# JTAG.net
KiCad netlist of a schematic drawn in Altium Designer
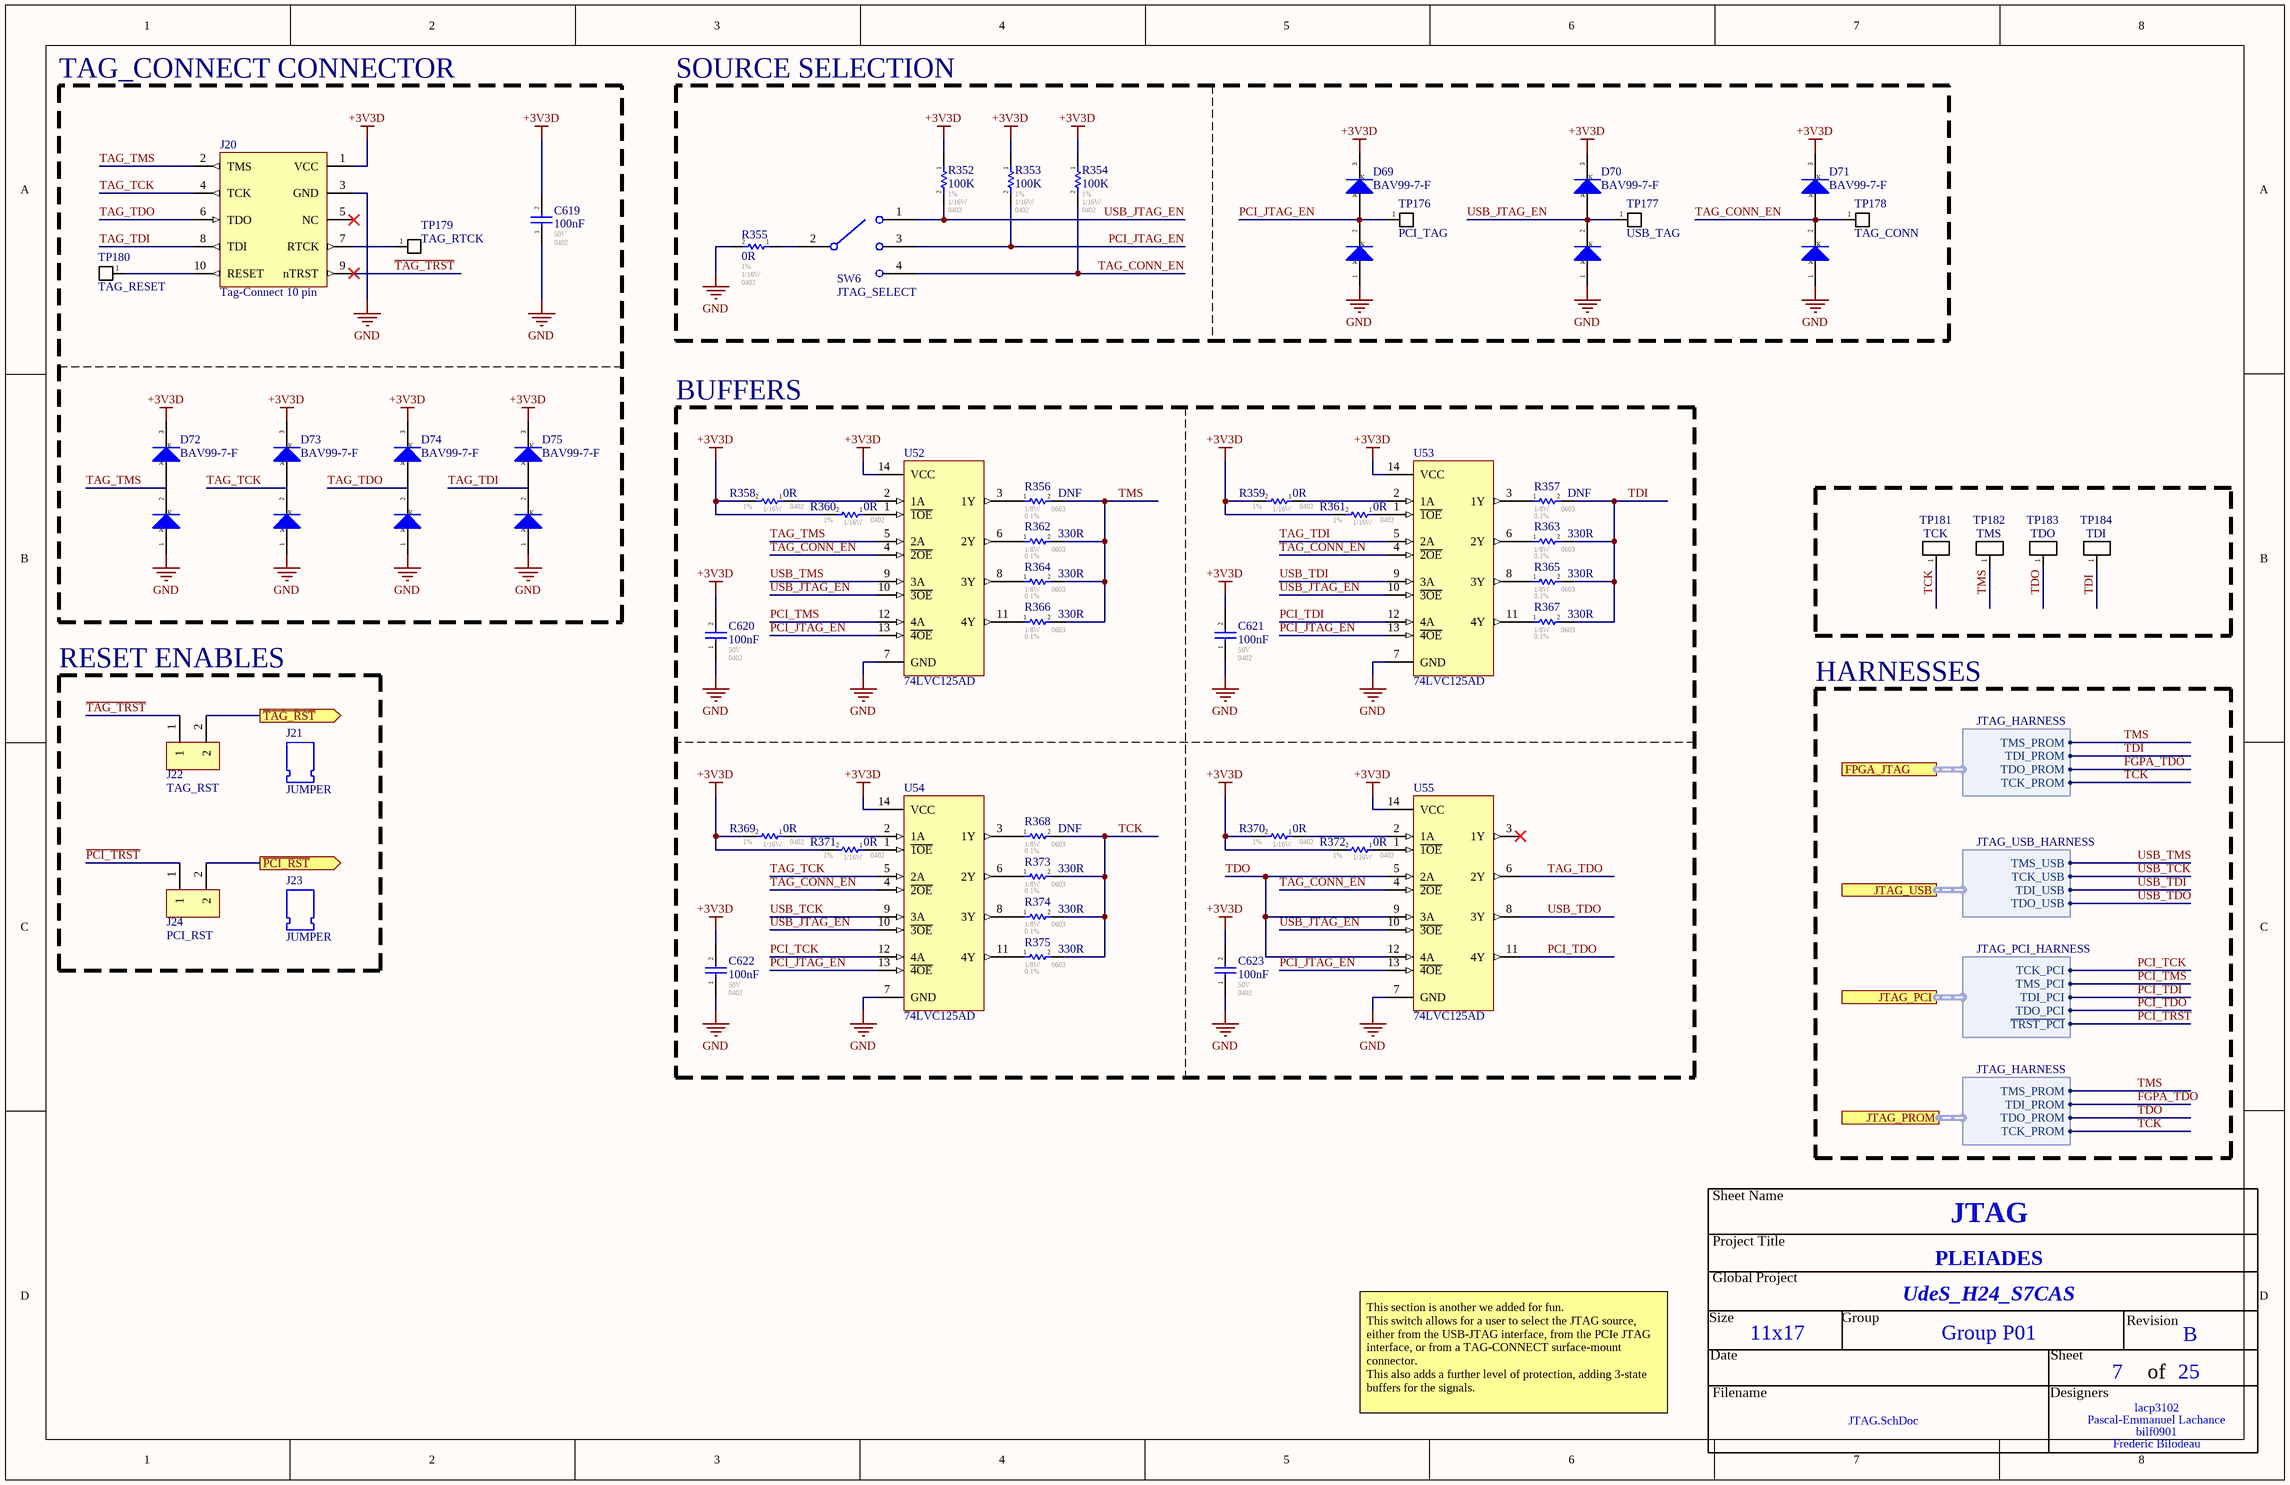
[diagram p0: JTAG.SchDoc]

(export (version "E")
  (design (tool "Eeschema 10.0.6"))
  (components
    (comp (ref "C619")
      (value "100nF")
      (footprint "0402")
      (description "GCM155R71H104KE02J\r\n0402 100nF 10% X7R Ceramic Capacitor")
      (fields
        (field (name "MFR") "Murata")
        (field (name "PART#") "GCM155R71H104KE02J")
        (field (name "VOLTAGE - RATED") "50V")
      )
      (libsource (lib "Symbols") (part "CAP_CER"))
    )
    (comp (ref "C620")
      (value "100nF")
      (footprint "0402")
      (description "GCM155R71H104KE02J\r\n0402 100nF 10% X7R Ceramic Capacitor")
      (fields
        (field (name "MFR") "Murata")
        (field (name "PART#") "GCM155R71H104KE02J")
        (field (name "VOLTAGE - RATED") "50V")
      )
      (libsource (lib "Symbols") (part "CAP_CER"))
    )
    (comp (ref "C621")
      (value "100nF")
      (footprint "0402")
      (description "GCM155R71H104KE02J\r\n0402 100nF 10% X7R Ceramic Capacitor")
      (fields
        (field (name "MFR") "Murata")
        (field (name "PART#") "GCM155R71H104KE02J")
        (field (name "VOLTAGE - RATED") "50V")
      )
      (libsource (lib "Symbols") (part "CAP_CER"))
    )
    (comp (ref "C622")
      (value "100nF")
      (footprint "0402")
      (description "GCM155R71H104KE02J\r\n0402 100nF 10% X7R Ceramic Capacitor")
      (fields
        (field (name "MFR") "Murata")
        (field (name "PART#") "GCM155R71H104KE02J")
        (field (name "VOLTAGE - RATED") "50V")
      )
      (libsource (lib "Symbols") (part "CAP_CER"))
    )
    (comp (ref "C623")
      (value "100nF")
      (footprint "0402")
      (description "GCM155R71H104KE02J\r\n0402 100nF 10% X7R Ceramic Capacitor")
      (fields
        (field (name "MFR") "Murata")
        (field (name "PART#") "GCM155R71H104KE02J")
        (field (name "VOLTAGE - RATED") "50V")
      )
      (libsource (lib "Symbols") (part "CAP_CER"))
    )
    (comp (ref "D69")
      (value "BAV99-7-F")
      (footprint "SOT23-3")
      (description "Diode Array 1 Pair Series Connection 75 V 300mA (DC) Surface Mount TO-236-3, SC-59, SOT-23-3")
      (fields (field (name "MFR") "Diodes Incorporated"))
      (libsource (lib "Symbols") (part "DIODE_TVS_DUAL"))
    )
    (comp (ref "D70")
      (value "BAV99-7-F")
      (footprint "SOT23-3")
      (description "Diode Array 1 Pair Series Connection 75 V 300mA (DC) Surface Mount TO-236-3, SC-59, SOT-23-3")
      (fields (field (name "MFR") "Diodes Incorporated"))
      (libsource (lib "Symbols") (part "DIODE_TVS_DUAL"))
    )
    (comp (ref "D71")
      (value "BAV99-7-F")
      (footprint "SOT23-3")
      (description "Diode Array 1 Pair Series Connection 75 V 300mA (DC) Surface Mount TO-236-3, SC-59, SOT-23-3")
      (fields (field (name "MFR") "Diodes Incorporated"))
      (libsource (lib "Symbols") (part "DIODE_TVS_DUAL"))
    )
    (comp (ref "D72")
      (value "BAV99-7-F")
      (footprint "SOT23-3")
      (description "Diode Array 1 Pair Series Connection 75 V 300mA (DC) Surface Mount TO-236-3, SC-59, SOT-23-3")
      (fields (field (name "MFR") "Diodes Incorporated"))
      (libsource (lib "Symbols") (part "DIODE_TVS_DUAL"))
    )
    (comp (ref "D73")
      (value "BAV99-7-F")
      (footprint "SOT23-3")
      (description "Diode Array 1 Pair Series Connection 75 V 300mA (DC) Surface Mount TO-236-3, SC-59, SOT-23-3")
      (fields (field (name "MFR") "Diodes Incorporated"))
      (libsource (lib "Symbols") (part "DIODE_TVS_DUAL"))
    )
    (comp (ref "D74")
      (value "BAV99-7-F")
      (footprint "SOT23-3")
      (description "Diode Array 1 Pair Series Connection 75 V 300mA (DC) Surface Mount TO-236-3, SC-59, SOT-23-3")
      (fields (field (name "MFR") "Diodes Incorporated"))
      (libsource (lib "Symbols") (part "DIODE_TVS_DUAL"))
    )
    (comp (ref "D75")
      (value "BAV99-7-F")
      (footprint "SOT23-3")
      (description "Diode Array 1 Pair Series Connection 75 V 300mA (DC) Surface Mount TO-236-3, SC-59, SOT-23-3")
      (fields (field (name "MFR") "Diodes Incorporated"))
      (libsource (lib "Symbols") (part "DIODE_TVS_DUAL"))
    )
    (comp (ref "J20")
      (value "Tag-Connect 10 pin")
      (footprint "TC2050-NL")
      (libsource (lib "Connectors") (part "TC2050-NL"))
    )
    (comp (ref "J21") (value "JUMPER") (libsource (lib "Misc") (part "JUMPER")))
    (comp (ref "J22")
      (value "TAG_RST")
      (footprint "HEADER-2_100MIL")
      (libsource (lib "Connectors") (part "HEADER_2"))
    )
    (comp (ref "J23") (value "JUMPER") (libsource (lib "Misc") (part "JUMPER")))
    (comp (ref "J24")
      (value "PCI_RST")
      (footprint "HEADER-2_100MIL")
      (libsource (lib "Connectors") (part "HEADER_2"))
    )
    (comp (ref "R352")
      (value "100K")
      (footprint "RES_0402")
      (fields
        (field (name "TOLERANCE") "1%")
        (field (name "POWER") "1/16W")
        (field (name "PACKAGE / CASE") "0402")
      )
      (libsource (lib "Symbols") (part "RESISTOR"))
    )
    (comp (ref "R353")
      (value "100K")
      (footprint "RES_0402")
      (fields
        (field (name "TOLERANCE") "1%")
        (field (name "POWER") "1/16W")
        (field (name "PACKAGE / CASE") "0402")
      )
      (libsource (lib "Symbols") (part "RESISTOR"))
    )
    (comp (ref "R354")
      (value "100K")
      (footprint "RES_0402")
      (fields
        (field (name "TOLERANCE") "1%")
        (field (name "POWER") "1/16W")
        (field (name "PACKAGE / CASE") "0402")
      )
      (libsource (lib "Symbols") (part "RESISTOR"))
    )
    (comp (ref "R355")
      (value "0R")
      (footprint "RES_0402")
      (fields
        (field (name "TOLERANCE") "1%")
        (field (name "POWER") "1/16W")
        (field (name "PACKAGE / CASE") "0402")
      )
      (libsource (lib "Symbols") (part "RESISTOR"))
    )
    (comp (ref "R356")
      (value "DNF")
      (footprint "RES_0603")
      (description "1M 0603 1% 1/16W Resistor")
      (fields
        (field (name "TOLERANCE") "0.1%")
        (field (name "POWER") "1/8W")
        (field (name "PACKAGE / CASE") "0603")
      )
      (libsource (lib "Symbols") (part "RESISTOR"))
    )
    (comp (ref "R357")
      (value "DNF")
      (footprint "RES_0603")
      (description "1M 0603 1% 1/16W Resistor")
      (fields
        (field (name "TOLERANCE") "0.1%")
        (field (name "POWER") "1/8W")
        (field (name "PACKAGE / CASE") "0603")
      )
      (libsource (lib "Symbols") (part "RESISTOR"))
    )
    (comp (ref "R358")
      (value "0R")
      (footprint "RES_0402")
      (fields
        (field (name "TOLERANCE") "1%")
        (field (name "POWER") "1/16W")
        (field (name "PACKAGE / CASE") "0402")
      )
      (libsource (lib "Symbols") (part "RESISTOR"))
    )
    (comp (ref "R359")
      (value "0R")
      (footprint "RES_0402")
      (fields
        (field (name "TOLERANCE") "1%")
        (field (name "POWER") "1/16W")
        (field (name "PACKAGE / CASE") "0402")
      )
      (libsource (lib "Symbols") (part "RESISTOR"))
    )
    (comp (ref "R360")
      (value "0R")
      (footprint "RES_0402")
      (fields
        (field (name "TOLERANCE") "1%")
        (field (name "POWER") "1/16W")
        (field (name "PACKAGE / CASE") "0402")
      )
      (libsource (lib "Symbols") (part "RESISTOR"))
    )
    (comp (ref "R361")
      (value "0R")
      (footprint "RES_0402")
      (fields
        (field (name "TOLERANCE") "1%")
        (field (name "POWER") "1/16W")
        (field (name "PACKAGE / CASE") "0402")
      )
      (libsource (lib "Symbols") (part "RESISTOR"))
    )
    (comp (ref "R362")
      (value "330R")
      (footprint "RES_0603")
      (description "1M 0603 1% 1/16W Resistor")
      (fields
        (field (name "TOLERANCE") "0.1%")
        (field (name "POWER") "1/8W")
        (field (name "PACKAGE / CASE") "0603")
      )
      (libsource (lib "Symbols") (part "RESISTOR"))
    )
    (comp (ref "R363")
      (value "330R")
      (footprint "RES_0603")
      (description "1M 0603 1% 1/16W Resistor")
      (fields
        (field (name "TOLERANCE") "0.1%")
        (field (name "POWER") "1/8W")
        (field (name "PACKAGE / CASE") "0603")
      )
      (libsource (lib "Symbols") (part "RESISTOR"))
    )
    (comp (ref "R364")
      (value "330R")
      (footprint "RES_0603")
      (description "1M 0603 1% 1/16W Resistor")
      (fields
        (field (name "TOLERANCE") "0.1%")
        (field (name "POWER") "1/8W")
        (field (name "PACKAGE / CASE") "0603")
      )
      (libsource (lib "Symbols") (part "RESISTOR"))
    )
    (comp (ref "R365")
      (value "330R")
      (footprint "RES_0603")
      (description "1M 0603 1% 1/16W Resistor")
      (fields
        (field (name "TOLERANCE") "0.1%")
        (field (name "POWER") "1/8W")
        (field (name "PACKAGE / CASE") "0603")
      )
      (libsource (lib "Symbols") (part "RESISTOR"))
    )
    (comp (ref "R366")
      (value "330R")
      (footprint "RES_0603")
      (description "1M 0603 1% 1/16W Resistor")
      (fields
        (field (name "TOLERANCE") "0.1%")
        (field (name "POWER") "1/8W")
        (field (name "PACKAGE / CASE") "0603")
      )
      (libsource (lib "Symbols") (part "RESISTOR"))
    )
    (comp (ref "R367")
      (value "330R")
      (footprint "RES_0603")
      (description "1M 0603 1% 1/16W Resistor")
      (fields
        (field (name "TOLERANCE") "0.1%")
        (field (name "POWER") "1/8W")
        (field (name "PACKAGE / CASE") "0603")
      )
      (libsource (lib "Symbols") (part "RESISTOR"))
    )
    (comp (ref "R368")
      (value "DNF")
      (footprint "RES_0603")
      (description "1M 0603 1% 1/16W Resistor")
      (fields
        (field (name "TOLERANCE") "0.1%")
        (field (name "POWER") "1/8W")
        (field (name "PACKAGE / CASE") "0603")
      )
      (libsource (lib "Symbols") (part "RESISTOR"))
    )
    (comp (ref "R369")
      (value "0R")
      (footprint "RES_0402")
      (fields
        (field (name "TOLERANCE") "1%")
        (field (name "POWER") "1/16W")
        (field (name "PACKAGE / CASE") "0402")
      )
      (libsource (lib "Symbols") (part "RESISTOR"))
    )
    (comp (ref "R370")
      (value "0R")
      (footprint "RES_0402")
      (fields
        (field (name "TOLERANCE") "1%")
        (field (name "POWER") "1/16W")
        (field (name "PACKAGE / CASE") "0402")
      )
      (libsource (lib "Symbols") (part "RESISTOR"))
    )
    (comp (ref "R371")
      (value "0R")
      (footprint "RES_0402")
      (fields
        (field (name "TOLERANCE") "1%")
        (field (name "POWER") "1/16W")
        (field (name "PACKAGE / CASE") "0402")
      )
      (libsource (lib "Symbols") (part "RESISTOR"))
    )
    (comp (ref "R372")
      (value "0R")
      (footprint "RES_0402")
      (fields
        (field (name "TOLERANCE") "1%")
        (field (name "POWER") "1/16W")
        (field (name "PACKAGE / CASE") "0402")
      )
      (libsource (lib "Symbols") (part "RESISTOR"))
    )
    (comp (ref "R373")
      (value "330R")
      (footprint "RES_0603")
      (description "1M 0603 1% 1/16W Resistor")
      (fields
        (field (name "TOLERANCE") "0.1%")
        (field (name "POWER") "1/8W")
        (field (name "PACKAGE / CASE") "0603")
      )
      (libsource (lib "Symbols") (part "RESISTOR"))
    )
    (comp (ref "R374")
      (value "330R")
      (footprint "RES_0603")
      (description "1M 0603 1% 1/16W Resistor")
      (fields
        (field (name "TOLERANCE") "0.1%")
        (field (name "POWER") "1/8W")
        (field (name "PACKAGE / CASE") "0603")
      )
      (libsource (lib "Symbols") (part "RESISTOR"))
    )
    (comp (ref "R375")
      (value "330R")
      (footprint "RES_0603")
      (description "1M 0603 1% 1/16W Resistor")
      (fields
        (field (name "TOLERANCE") "0.1%")
        (field (name "POWER") "1/8W")
        (field (name "PACKAGE / CASE") "0603")
      )
      (libsource (lib "Symbols") (part "RESISTOR"))
    )
    (comp (ref "SW6")
      (value "JTAG_SELECT")
      (footprint "1825256-6")
      (description "1825256-6\r\nSlide Switch SP3T Through Hole, Right Angle")
      (fields (field (name "MFR") "TE Connectivity"))
      (libsource (lib "Symbols") (part "SP3T_SWITCH"))
    )
    (comp (ref "TP176")
      (value "PCI_TAG")
      (footprint "TP_PAD")
      (description "Test Point")
      (libsource (lib "Symbols") (part "TESTPOINT_PAD"))
    )
    (comp (ref "TP177")
      (value "USB_TAG")
      (footprint "TP_PAD")
      (description "Test Point")
      (libsource (lib "Symbols") (part "TESTPOINT_PAD"))
    )
    (comp (ref "TP178")
      (value "TAG_CONN")
      (footprint "TP_PAD")
      (description "Test Point")
      (libsource (lib "Symbols") (part "TESTPOINT_PAD"))
    )
    (comp (ref "TP179")
      (value "TAG_RTCK")
      (footprint "TP_PAD")
      (description "Test Point")
      (libsource (lib "Symbols") (part "TESTPOINT_PAD"))
    )
    (comp (ref "TP180")
      (value "TAG_RESET")
      (footprint "TP_PAD")
      (description "Test Point")
      (libsource (lib "Symbols") (part "TESTPOINT_PAD"))
    )
    (comp (ref "TP181")
      (value "TCK")
      (footprint "TP_HOLE")
      (description "Test Point")
      (libsource (lib "Symbols") (part "TESTPOINT"))
    )
    (comp (ref "TP182")
      (value "TMS")
      (footprint "TP_HOLE")
      (description "Test Point")
      (libsource (lib "Symbols") (part "TESTPOINT"))
    )
    (comp (ref "TP183")
      (value "TDO")
      (footprint "TP_HOLE")
      (description "Test Point")
      (libsource (lib "Symbols") (part "TESTPOINT"))
    )
    (comp (ref "TP184")
      (value "TDI")
      (footprint "TP_HOLE")
      (description "Test Point")
      (libsource (lib "Symbols") (part "TESTPOINT"))
    )
    (comp (ref "U52")
      (value "74LVC125AD")
      (footprint "SOIC-14_3.8MM")
      (description "Buffer, Non-Inverting 4 Element 1 Bit per Element 3-State Output 14-SO")
      (fields (field (name "MFR") "Nexperia"))
      (libsource (lib "Misc") (part "74LVC125AD,118"))
    )
    (comp (ref "U53")
      (value "74LVC125AD")
      (footprint "SOIC-14_3.8MM")
      (description "Buffer, Non-Inverting 4 Element 1 Bit per Element 3-State Output 14-SO")
      (fields (field (name "MFR") "Nexperia"))
      (libsource (lib "Misc") (part "74LVC125AD,118"))
    )
    (comp (ref "U54")
      (value "74LVC125AD")
      (footprint "SOIC-14_3.8MM")
      (description "Buffer, Non-Inverting 4 Element 1 Bit per Element 3-State Output 14-SO")
      (fields (field (name "MFR") "Nexperia"))
      (libsource (lib "Misc") (part "74LVC125AD,118"))
    )
    (comp (ref "U55")
      (value "74LVC125AD")
      (footprint "SOIC-14_3.8MM")
      (description "Buffer, Non-Inverting 4 Element 1 Bit per Element 3-State Output 14-SO")
      (fields (field (name "MFR") "Nexperia"))
      (libsource (lib "Misc") (part "74LVC125AD,118"))
    )
  )
  (nets
    (net (code "4") (name "+3V3D") (class "Default")
      (node (ref "C619") (pin "2") (pinfunction "2_2") (pintype "passive"))
      (node (ref "C620") (pin "2") (pinfunction "2_2") (pintype "passive"))
      (node (ref "C621") (pin "2") (pinfunction "2_2") (pintype "passive"))
      (node (ref "C622") (pin "2") (pinfunction "2_2") (pintype "passive"))
      (node (ref "C623") (pin "2") (pinfunction "2_2") (pintype "passive"))
      (node (ref "D69") (pin "3") (pinfunction "K_3") (pintype "passive"))
      (node (ref "D70") (pin "3") (pinfunction "K_3") (pintype "passive"))
      (node (ref "D71") (pin "3") (pinfunction "K_3") (pintype "passive"))
      (node (ref "D72") (pin "3") (pinfunction "K_3") (pintype "passive"))
      (node (ref "D73") (pin "3") (pinfunction "K_3") (pintype "passive"))
      (node (ref "D74") (pin "3") (pinfunction "K_3") (pintype "passive"))
      (node (ref "D75") (pin "3") (pinfunction "K_3") (pintype "passive"))
      (node (ref "J20") (pin "1") (pinfunction "VCC_1") (pintype "power_in"))
      (node (ref "R352") (pin "1") (pinfunction "1_1") (pintype "passive"))
      (node (ref "R353") (pin "1") (pinfunction "1_1") (pintype "passive"))
      (node (ref "R354") (pin "1") (pinfunction "1_1") (pintype "passive"))
      (node (ref "R358") (pin "2") (pinfunction "2_2") (pintype "passive"))
      (node (ref "R359") (pin "2") (pinfunction "2_2") (pintype "passive"))
      (node (ref "R360") (pin "2") (pinfunction "2_2") (pintype "passive"))
      (node (ref "R361") (pin "2") (pinfunction "2_2") (pintype "passive"))
      (node (ref "R369") (pin "2") (pinfunction "2_2") (pintype "passive"))
      (node (ref "R370") (pin "2") (pinfunction "2_2") (pintype "passive"))
      (node (ref "R371") (pin "2") (pinfunction "2_2") (pintype "passive"))
      (node (ref "R372") (pin "2") (pinfunction "2_2") (pintype "passive"))
      (node (ref "U52") (pin "14") (pinfunction "VCC_14") (pintype "power_in"))
      (node (ref "U53") (pin "14") (pinfunction "VCC_14") (pintype "power_in"))
      (node (ref "U54") (pin "14") (pinfunction "VCC_14") (pintype "power_in"))
      (node (ref "U55") (pin "14") (pinfunction "VCC_14") (pintype "power_in"))
    )
    (net (code "6") (name "/PCI_JTAG_EN") (class "Default")
      (node (ref "D69") (pin "2") (pinfunction "K_2") (pintype "passive"))
      (node (ref "R353") (pin "2") (pinfunction "2_2") (pintype "passive"))
      (node (ref "SW6") (pin "3") (pinfunction "3_3") (pintype "passive"))
      (node (ref "TP176") (pin "1") (pinfunction "A_1") (pintype "passive"))
      (node (ref "U52") (pin "13") (pinfunction "4OE_13") (pintype "input"))
      (node (ref "U53") (pin "13") (pinfunction "4OE_13") (pintype "input"))
      (node (ref "U54") (pin "13") (pinfunction "4OE_13") (pintype "input"))
      (node (ref "U55") (pin "13") (pinfunction "4OE_13") (pintype "input"))
    )
    (net (code "7") (name "/PCI_RST") (class "Default")
      (node (ref "J24") (pin "2") (pinfunction "2_2") (pintype "passive"))
    )
    (net (code "8") (name "/PCI_TCK") (class "Default")
      (node (ref "U54") (pin "12") (pinfunction "4A_12") (pintype "input"))
    )
    (net (code "9") (name "/PCI_TDI") (class "Default")
      (node (ref "U53") (pin "12") (pinfunction "4A_12") (pintype "input"))
    )
    (net (code "10") (name "/PCI_TDO") (class "Default")
      (node (ref "U55") (pin "11") (pinfunction "4Y_11") (pintype "output"))
    )
    (net (code "11") (name "/PCI_TMS") (class "Default")
      (node (ref "U52") (pin "12") (pinfunction "4A_12") (pintype "input"))
    )
    (net (code "12") (name "/PCI_TRST") (class "Default")
      (node (ref "J24") (pin "1") (pinfunction "1_1") (pintype "passive"))
    )
    (net (code "13") (name "/TAG_CONN_EN") (class "Default")
      (node (ref "D71") (pin "2") (pinfunction "K_2") (pintype "passive"))
      (node (ref "R354") (pin "2") (pinfunction "2_2") (pintype "passive"))
      (node (ref "SW6") (pin "4") (pinfunction "4_4") (pintype "passive"))
      (node (ref "TP178") (pin "1") (pinfunction "A_1") (pintype "passive"))
      (node (ref "U52") (pin "4") (pinfunction "2OE_4") (pintype "input"))
      (node (ref "U53") (pin "4") (pinfunction "2OE_4") (pintype "input"))
      (node (ref "U54") (pin "4") (pinfunction "2OE_4") (pintype "input"))
      (node (ref "U55") (pin "4") (pinfunction "2OE_4") (pintype "input"))
    )
    (net (code "14") (name "/TAG_RST") (class "Default")
      (node (ref "J22") (pin "2") (pinfunction "2_2") (pintype "passive"))
    )
    (net (code "15") (name "/TAG_TCK") (class "Default")
      (node (ref "D73") (pin "2") (pinfunction "K_2") (pintype "passive"))
      (node (ref "J20") (pin "4") (pinfunction "TCK_4") (pintype "output"))
      (node (ref "U54") (pin "5") (pinfunction "2A_5") (pintype "input"))
    )
    (net (code "16") (name "/TAG_TDI") (class "Default")
      (node (ref "D75") (pin "2") (pinfunction "K_2") (pintype "passive"))
      (node (ref "J20") (pin "8") (pinfunction "TDI_8") (pintype "output"))
      (node (ref "U53") (pin "5") (pinfunction "2A_5") (pintype "input"))
    )
    (net (code "17") (name "/TAG_TDO") (class "Default")
      (node (ref "D74") (pin "2") (pinfunction "K_2") (pintype "passive"))
      (node (ref "J20") (pin "6") (pinfunction "TDO_6") (pintype "input"))
      (node (ref "U55") (pin "6") (pinfunction "2Y_6") (pintype "output"))
    )
    (net (code "18") (name "/TAG_TMS") (class "Default")
      (node (ref "D72") (pin "2") (pinfunction "K_2") (pintype "passive"))
      (node (ref "J20") (pin "2") (pinfunction "TMS_2") (pintype "output"))
      (node (ref "U52") (pin "5") (pinfunction "2A_5") (pintype "input"))
    )
    (net (code "19") (name "/TAG_TRST") (class "Default")
      (node (ref "J20") (pin "9") (pinfunction "nTRST_9") (pintype "output"))
      (node (ref "J22") (pin "1") (pinfunction "1_1") (pintype "passive"))
    )
    (net (code "20") (name "/TCK") (class "Default")
      (node (ref "R368") (pin "2") (pinfunction "2_2") (pintype "passive"))
      (node (ref "R373") (pin "2") (pinfunction "2_2") (pintype "passive"))
      (node (ref "R374") (pin "2") (pinfunction "2_2") (pintype "passive"))
      (node (ref "R375") (pin "2") (pinfunction "2_2") (pintype "passive"))
      (node (ref "TP181") (pin "1") (pinfunction "A_1") (pintype "passive"))
    )
    (net (code "21") (name "/TDI") (class "Default")
      (node (ref "R357") (pin "2") (pinfunction "2_2") (pintype "passive"))
      (node (ref "R363") (pin "2") (pinfunction "2_2") (pintype "passive"))
      (node (ref "R365") (pin "2") (pinfunction "2_2") (pintype "passive"))
      (node (ref "R367") (pin "2") (pinfunction "2_2") (pintype "passive"))
      (node (ref "TP184") (pin "1") (pinfunction "A_1") (pintype "passive"))
    )
    (net (code "22") (name "/TDO") (class "Default")
      (node (ref "TP183") (pin "1") (pinfunction "A_1") (pintype "passive"))
      (node (ref "U55") (pin "12") (pinfunction "4A_12") (pintype "input"))
      (node (ref "U55") (pin "5") (pinfunction "2A_5") (pintype "input"))
      (node (ref "U55") (pin "9") (pinfunction "3A_9") (pintype "input"))
    )
    (net (code "23") (name "/TMS") (class "Default")
      (node (ref "R356") (pin "2") (pinfunction "2_2") (pintype "passive"))
      (node (ref "R362") (pin "2") (pinfunction "2_2") (pintype "passive"))
      (node (ref "R364") (pin "2") (pinfunction "2_2") (pintype "passive"))
      (node (ref "R366") (pin "2") (pinfunction "2_2") (pintype "passive"))
      (node (ref "TP182") (pin "1") (pinfunction "A_1") (pintype "passive"))
    )
    (net (code "24") (name "/USB_JTAG_EN") (class "Default")
      (node (ref "D70") (pin "2") (pinfunction "K_2") (pintype "passive"))
      (node (ref "R352") (pin "2") (pinfunction "2_2") (pintype "passive"))
      (node (ref "SW6") (pin "1") (pinfunction "1_1") (pintype "passive"))
      (node (ref "TP177") (pin "1") (pinfunction "A_1") (pintype "passive"))
      (node (ref "U52") (pin "10") (pinfunction "3OE_10") (pintype "input"))
      (node (ref "U53") (pin "10") (pinfunction "3OE_10") (pintype "input"))
      (node (ref "U54") (pin "10") (pinfunction "3OE_10") (pintype "input"))
      (node (ref "U55") (pin "10") (pinfunction "3OE_10") (pintype "input"))
    )
    (net (code "25") (name "/USB_TCK") (class "Default")
      (node (ref "U54") (pin "9") (pinfunction "3A_9") (pintype "input"))
    )
    (net (code "26") (name "/USB_TDI") (class "Default")
      (node (ref "U53") (pin "9") (pinfunction "3A_9") (pintype "input"))
    )
    (net (code "27") (name "/USB_TDO") (class "Default")
      (node (ref "U55") (pin "8") (pinfunction "3Y_8") (pintype "output"))
    )
    (net (code "28") (name "/USB_TMS") (class "Default")
      (node (ref "U52") (pin "9") (pinfunction "3A_9") (pintype "input"))
    )
    (net (code "32") (name "GND") (class "Default")
      (node (ref "C619") (pin "1") (pinfunction "1_1") (pintype "passive"))
      (node (ref "C620") (pin "1") (pinfunction "1_1") (pintype "passive"))
      (node (ref "C621") (pin "1") (pinfunction "1_1") (pintype "passive"))
      (node (ref "C622") (pin "1") (pinfunction "1_1") (pintype "passive"))
      (node (ref "C623") (pin "1") (pinfunction "1_1") (pintype "passive"))
      (node (ref "D69") (pin "1") (pinfunction "A_1") (pintype "passive"))
      (node (ref "D70") (pin "1") (pinfunction "A_1") (pintype "passive"))
      (node (ref "D71") (pin "1") (pinfunction "A_1") (pintype "passive"))
      (node (ref "D72") (pin "1") (pinfunction "A_1") (pintype "passive"))
      (node (ref "D73") (pin "1") (pinfunction "A_1") (pintype "passive"))
      (node (ref "D74") (pin "1") (pinfunction "A_1") (pintype "passive"))
      (node (ref "D75") (pin "1") (pinfunction "A_1") (pintype "passive"))
      (node (ref "J20") (pin "3") (pinfunction "GND_3") (pintype "power_in"))
      (node (ref "R355") (pin "2") (pinfunction "2_2") (pintype "passive"))
      (node (ref "U52") (pin "7") (pinfunction "GND_7") (pintype "power_in"))
      (node (ref "U53") (pin "7") (pinfunction "GND_7") (pintype "power_in"))
      (node (ref "U54") (pin "7") (pinfunction "GND_7") (pintype "power_in"))
      (node (ref "U55") (pin "7") (pinfunction "GND_7") (pintype "power_in"))
    )
    (net (code "33") (name "Net-(J20-RESET)") (class "Default")
      (node (ref "J20") (pin "10") (pinfunction "RESET_10") (pintype "output"))
      (node (ref "TP180") (pin "1") (pinfunction "A_1") (pintype "passive"))
    )
    (net (code "34") (name "Net-(J20-RTCK)") (class "Default")
      (node (ref "J20") (pin "7") (pinfunction "RTCK_7") (pintype "output"))
      (node (ref "TP179") (pin "1") (pinfunction "A_1") (pintype "passive"))
    )
    (net (code "35") (name "Net-(R355-Pad1)") (class "Default")
      (node (ref "R355") (pin "1") (pinfunction "1_1") (pintype "passive"))
      (node (ref "SW6") (pin "2") (pinfunction "2_2") (pintype "passive"))
    )
    (net (code "36") (name "Net-(U52-1A)") (class "Default")
      (node (ref "R358") (pin "1") (pinfunction "1_1") (pintype "passive"))
      (node (ref "U52") (pin "2") (pinfunction "1A_2") (pintype "input"))
    )
    (net (code "37") (name "Net-(U52-1OE)") (class "Default")
      (node (ref "R360") (pin "1") (pinfunction "1_1") (pintype "passive"))
      (node (ref "U52") (pin "1") (pinfunction "1OE_1") (pintype "input"))
    )
    (net (code "38") (name "Net-(U52-1Y)") (class "Default")
      (node (ref "R356") (pin "1") (pinfunction "1_1") (pintype "passive"))
      (node (ref "U52") (pin "3") (pinfunction "1Y_3") (pintype "output"))
    )
    (net (code "39") (name "Net-(U52-2Y)") (class "Default")
      (node (ref "R362") (pin "1") (pinfunction "1_1") (pintype "passive"))
      (node (ref "U52") (pin "6") (pinfunction "2Y_6") (pintype "output"))
    )
    (net (code "40") (name "Net-(U52-3Y)") (class "Default")
      (node (ref "R364") (pin "1") (pinfunction "1_1") (pintype "passive"))
      (node (ref "U52") (pin "8") (pinfunction "3Y_8") (pintype "output"))
    )
    (net (code "41") (name "Net-(U52-4Y)") (class "Default")
      (node (ref "R366") (pin "1") (pinfunction "1_1") (pintype "passive"))
      (node (ref "U52") (pin "11") (pinfunction "4Y_11") (pintype "output"))
    )
    (net (code "42") (name "Net-(U53-1A)") (class "Default")
      (node (ref "R359") (pin "1") (pinfunction "1_1") (pintype "passive"))
      (node (ref "U53") (pin "2") (pinfunction "1A_2") (pintype "input"))
    )
    (net (code "43") (name "Net-(U53-1OE)") (class "Default")
      (node (ref "R361") (pin "1") (pinfunction "1_1") (pintype "passive"))
      (node (ref "U53") (pin "1") (pinfunction "1OE_1") (pintype "input"))
    )
    (net (code "44") (name "Net-(U53-1Y)") (class "Default")
      (node (ref "R357") (pin "1") (pinfunction "1_1") (pintype "passive"))
      (node (ref "U53") (pin "3") (pinfunction "1Y_3") (pintype "output"))
    )
    (net (code "45") (name "Net-(U53-2Y)") (class "Default")
      (node (ref "R363") (pin "1") (pinfunction "1_1") (pintype "passive"))
      (node (ref "U53") (pin "6") (pinfunction "2Y_6") (pintype "output"))
    )
    (net (code "46") (name "Net-(U53-3Y)") (class "Default")
      (node (ref "R365") (pin "1") (pinfunction "1_1") (pintype "passive"))
      (node (ref "U53") (pin "8") (pinfunction "3Y_8") (pintype "output"))
    )
    (net (code "47") (name "Net-(U53-4Y)") (class "Default")
      (node (ref "R367") (pin "1") (pinfunction "1_1") (pintype "passive"))
      (node (ref "U53") (pin "11") (pinfunction "4Y_11") (pintype "output"))
    )
    (net (code "48") (name "Net-(U54-1A)") (class "Default")
      (node (ref "R369") (pin "1") (pinfunction "1_1") (pintype "passive"))
      (node (ref "U54") (pin "2") (pinfunction "1A_2") (pintype "input"))
    )
    (net (code "49") (name "Net-(U54-1OE)") (class "Default")
      (node (ref "R371") (pin "1") (pinfunction "1_1") (pintype "passive"))
      (node (ref "U54") (pin "1") (pinfunction "1OE_1") (pintype "input"))
    )
    (net (code "50") (name "Net-(U54-1Y)") (class "Default")
      (node (ref "R368") (pin "1") (pinfunction "1_1") (pintype "passive"))
      (node (ref "U54") (pin "3") (pinfunction "1Y_3") (pintype "output"))
    )
    (net (code "51") (name "Net-(U54-2Y)") (class "Default")
      (node (ref "R373") (pin "1") (pinfunction "1_1") (pintype "passive"))
      (node (ref "U54") (pin "6") (pinfunction "2Y_6") (pintype "output"))
    )
    (net (code "52") (name "Net-(U54-3Y)") (class "Default")
      (node (ref "R374") (pin "1") (pinfunction "1_1") (pintype "passive"))
      (node (ref "U54") (pin "8") (pinfunction "3Y_8") (pintype "output"))
    )
    (net (code "53") (name "Net-(U54-4Y)") (class "Default")
      (node (ref "R375") (pin "1") (pinfunction "1_1") (pintype "passive"))
      (node (ref "U54") (pin "11") (pinfunction "4Y_11") (pintype "output"))
    )
    (net (code "54") (name "Net-(U55-1A)") (class "Default")
      (node (ref "R370") (pin "1") (pinfunction "1_1") (pintype "passive"))
      (node (ref "U55") (pin "2") (pinfunction "1A_2") (pintype "input"))
    )
    (net (code "55") (name "Net-(U55-1OE)") (class "Default")
      (node (ref "R372") (pin "1") (pinfunction "1_1") (pintype "passive"))
      (node (ref "U55") (pin "1") (pinfunction "1OE_1") (pintype "input"))
    )
    (net (code "56") (name "unconnected-(J20-NC-Pad5)") (class "Default")
      (node (ref "J20") (pin "5") (pinfunction "NC_5") (pintype "passive+no_connect"))
    )
    (net (code "57") (name "unconnected-(U55-1Y-Pad3)") (class "Default")
      (node (ref "U55") (pin "3") (pinfunction "1Y_3") (pintype "output+no_connect"))
    )
  )
)
